# 411_AutoFan_New.net
KiCad netlist of a schematic drawn in EAGLE
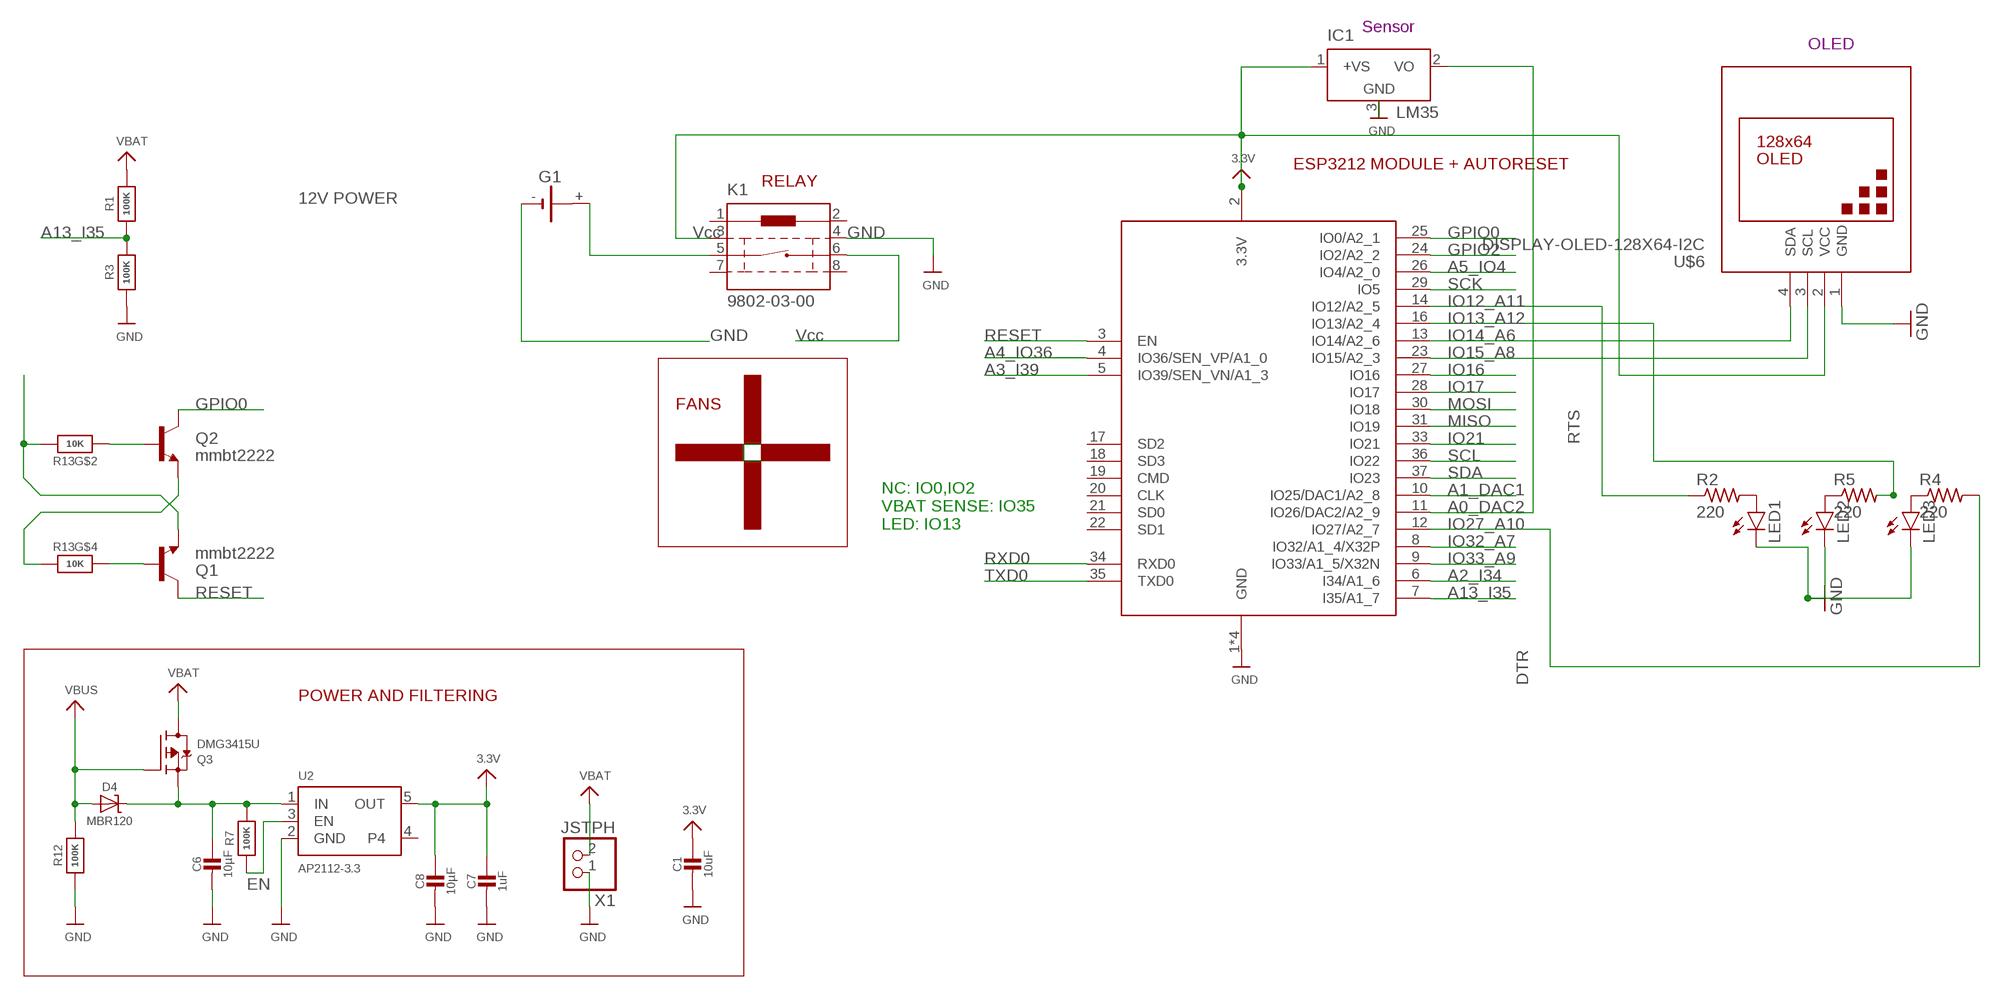
[diagram p0: schematic, sheet 1]

(export (version "E")
  (design (tool "Eeschema 10.0.6"))
  (components
    (comp (ref "C1")
      (value "10uF")
      (footprint "eagle-import:0805-NO")
      (libsource (lib "eagle-import") (part "CAP_CERAMIC0805-NOOUTLINE"))
    )
    (comp (ref "C6")
      (value "10µF")
      (footprint "eagle-import:0805-NO")
      (libsource (lib "eagle-import") (part "CAP_CERAMIC0805-NOOUTLINE"))
    )
    (comp (ref "C7")
      (value "1uF")
      (footprint "eagle-import:0603-NO")
      (libsource (lib "eagle-import") (part "CAP_CERAMIC0603_NO"))
    )
    (comp (ref "C8")
      (value "10µF")
      (footprint "eagle-import:0805-NO")
      (libsource (lib "eagle-import") (part "CAP_CERAMIC0805-NOOUTLINE"))
    )
    (comp (ref "D4")
      (value "MBR120")
      (footprint "eagle-import:SOD-123")
      (libsource (lib "eagle-import") (part "DIODE-SCHOTTKYSOD-123"))
    )
    (comp (ref "G1")
      (value "CR2032V")
      (footprint "eagle-import:CR2032V")
      (libsource (lib "eagle-import") (part "CR2032V"))
    )
    (comp (ref "IC1")
      (value "LM50")
      (footprint "eagle-import:SOT23")
      (libsource (lib "eagle-import") (part "LM50"))
    )
    (comp (ref "K1")
      (value "9802-03-00")
      (footprint "eagle-import:9802-00")
      (libsource (lib "eagle-import") (part "9802-00-03"))
    )
    (comp (ref "LED1")
      (value "LED5MM")
      (footprint "eagle-import:LED5MM")
      (libsource (lib "eagle-import") (part "LED5MM"))
    )
    (comp (ref "LED2")
      (value "LED5MM")
      (footprint "eagle-import:LED5MM")
      (libsource (lib "eagle-import") (part "LED5MM"))
    )
    (comp (ref "LED3")
      (value "LED5MM")
      (footprint "eagle-import:LED5MM")
      (libsource (lib "eagle-import") (part "LED5MM"))
    )
    (comp (ref "Q1")
      (value "mmbt2222")
      (footprint "eagle-import:SOT23-3")
      (libsource (lib "eagle-import") (part "TRANSISTOR_NPNSOT23-3"))
    )
    (comp (ref "Q2")
      (value "mmbt2222")
      (footprint "eagle-import:SOT23-3")
      (libsource (lib "eagle-import") (part "TRANSISTOR_NPNSOT23-3"))
    )
    (comp (ref "Q3")
      (value "DMG3415U")
      (footprint "eagle-import:SOT23-R")
      (libsource (lib "eagle-import") (part "MOSFET-P"))
    )
    (comp (ref "R1")
      (value "100K")
      (footprint "eagle-import:0603-NO")
      (libsource (lib "eagle-import") (part "RESISTOR_0603_NOOUT"))
    )
    (comp (ref "R2")
      (value "220")
      (footprint "eagle-import:0204_7")
      (libsource (lib "eagle-import") (part "R-US_0204/7"))
    )
    (comp (ref "R3")
      (value "100K")
      (footprint "eagle-import:0603-NO")
      (libsource (lib "eagle-import") (part "RESISTOR_0603_NOOUT"))
    )
    (comp (ref "R4")
      (value "220")
      (footprint "eagle-import:0204_7")
      (libsource (lib "eagle-import") (part "R-US_0204/7"))
    )
    (comp (ref "R5")
      (value "220")
      (footprint "eagle-import:0204_7")
      (libsource (lib "eagle-import") (part "R-US_0204/7"))
    )
    (comp (ref "R7")
      (value "100K")
      (footprint "eagle-import:0603-NO")
      (libsource (lib "eagle-import") (part "RESISTOR_0603_NOOUT"))
    )
    (comp (ref "R12")
      (value "100K")
      (footprint "eagle-import:0603-NO")
      (libsource (lib "eagle-import") (part "RESISTOR_0603_NOOUT"))
    )
    (comp (ref "R13")
      (value "10K")
      (footprint "eagle-import:RESPACK_4X0603")
      (libsource (lib "eagle-import") (part "RESISTOR_4PACK"))
    )
    (comp (ref "U$6")
      (value "DISPLAY-OLED-128X64-I2C")
      (footprint "eagle-import:DISPLAY-OLED-128X64-I2C")
      (libsource (lib "eagle-import") (part "DISPLAY-OLED-128X64-I2C"))
    )
    (comp (ref "U2")
      (value "AP2112-3.3")
      (footprint "eagle-import:SOT23-5")
      (libsource (lib "eagle-import") (part "VREG_SOT23-5"))
    )
    (comp (ref "X1")
      (value "JSTPH")
      (footprint "eagle-import:JSTPH2")
      (libsource (lib "eagle-import") (part "CON_JST_PH_2PIN"))
    )
    (comp (ref "X2")
      (value "ESP32_WROOM32_SKINNY")
      (footprint "eagle-import:WROOM32_SKINNY")
      (libsource (lib "eagle-import") (part "ESP32_WROOM32_SKINNY"))
    )
  )
  (nets
    (net (code "1") (name "/A0_DAC2") (class "Default")
      (node (ref "IC1") (pin "2") (pinfunction "VO_2") (pintype "input"))
      (node (ref "X2") (pin "11") (pinfunction "IO26/DAC2/A2_9_11") (pintype "bidirectional"))
    )
    (net (code "2") (name "/A1_DAC1") (class "Default")
      (node (ref "X2") (pin "10") (pinfunction "IO25/DAC1/A2_8_10") (pintype "bidirectional"))
    )
    (net (code "3") (name "/A2_I34") (class "Default")
      (node (ref "X2") (pin "6") (pinfunction "I34/A1_6_6") (pintype "bidirectional"))
    )
    (net (code "4") (name "/A3_I39") (class "Default")
      (node (ref "X2") (pin "5") (pinfunction "IO39/SEN_VN/A1_3_5") (pintype "passive"))
    )
    (net (code "5") (name "/A4_IO36") (class "Default")
      (node (ref "X2") (pin "4") (pinfunction "IO36/SEN_VP/A1_0_4") (pintype "passive"))
    )
    (net (code "6") (name "/A5_IO4") (class "Default")
      (node (ref "X2") (pin "26") (pinfunction "IO4/A2_0_26") (pintype "bidirectional"))
    )
    (net (code "7") (name "/A13_I35") (class "Default")
      (node (ref "R1") (pin "1") (pinfunction "1_1") (pintype "passive"))
      (node (ref "R3") (pin "2") (pinfunction "2_2") (pintype "passive"))
      (node (ref "X2") (pin "7") (pinfunction "I35/A1_7_7") (pintype "bidirectional"))
    )
    (net (code "8") (name "/DTR") (class "Default")
      (node (ref "Q2") (pin "2") (pinfunction "E_2") (pintype "passive"))
      (node (ref "R13") (pin "4") (pinfunction "1_4") (pintype "passive"))
    )
    (net (code "9") (name "/EN") (class "Default")
      (node (ref "R7") (pin "1") (pinfunction "1_1") (pintype "passive"))
      (node (ref "U2") (pin "3") (pinfunction "EN_3") (pintype "input"))
    )
    (net (code "10") (name "/GPIO0") (class "Default")
      (node (ref "Q2") (pin "3") (pinfunction "C_3") (pintype "passive"))
      (node (ref "X2") (pin "25") (pinfunction "IO0/A2_1_25") (pintype "bidirectional"))
    )
    (net (code "11") (name "/GPIO2") (class "Default")
      (node (ref "X2") (pin "24") (pinfunction "IO2/A2_2_24") (pintype "bidirectional"))
    )
    (net (code "12") (name "/IO12_A11") (class "Default")
      (node (ref "R2") (pin "1") (pinfunction "1_1") (pintype "passive"))
      (node (ref "X2") (pin "14") (pinfunction "IO12/A2_5_14") (pintype "bidirectional"))
    )
    (net (code "13") (name "/IO13_A12") (class "Default")
      (node (ref "R5") (pin "2") (pinfunction "2_2") (pintype "passive"))
      (node (ref "X2") (pin "16") (pinfunction "IO13/A2_4_16") (pintype "bidirectional"))
    )
    (net (code "14") (name "/IO14_A6") (class "Default")
      (node (ref "U$6") (pin "4") (pinfunction "SDA_4") (pintype "bidirectional"))
      (node (ref "X2") (pin "13") (pinfunction "IO14/A2_6_13") (pintype "bidirectional"))
    )
    (net (code "15") (name "/IO15_A8") (class "Default")
      (node (ref "U$6") (pin "3") (pinfunction "SCL_3") (pintype "bidirectional"))
      (node (ref "X2") (pin "23") (pinfunction "IO15/A2_3_23") (pintype "bidirectional"))
    )
    (net (code "16") (name "/IO16") (class "Default")
      (node (ref "X2") (pin "27") (pinfunction "IO16_27") (pintype "bidirectional"))
    )
    (net (code "17") (name "/IO17") (class "Default")
      (node (ref "X2") (pin "28") (pinfunction "IO17_28") (pintype "bidirectional"))
    )
    (net (code "18") (name "/IO21") (class "Default")
      (node (ref "X2") (pin "33") (pinfunction "IO21_33") (pintype "bidirectional"))
    )
    (net (code "19") (name "/IO27_A10") (class "Default")
      (node (ref "R4") (pin "2") (pinfunction "2_2") (pintype "passive"))
      (node (ref "X2") (pin "12") (pinfunction "IO27/A2_7_12") (pintype "bidirectional"))
    )
    (net (code "20") (name "/IO32_A7") (class "Default")
      (node (ref "X2") (pin "8") (pinfunction "IO32/A1_4/X32P_8") (pintype "bidirectional"))
    )
    (net (code "21") (name "/IO33_A9") (class "Default")
      (node (ref "X2") (pin "9") (pinfunction "IO33/A1_5/X32N_9") (pintype "bidirectional"))
    )
    (net (code "22") (name "/MISO") (class "Default")
      (node (ref "X2") (pin "31") (pinfunction "IO19_31") (pintype "bidirectional"))
    )
    (net (code "23") (name "/MOSI") (class "Default")
      (node (ref "X2") (pin "30") (pinfunction "IO18_30") (pintype "bidirectional"))
    )
    (net (code "24") (name "/RESET") (class "Default")
      (node (ref "Q1") (pin "3") (pinfunction "C_3") (pintype "passive"))
      (node (ref "X2") (pin "3") (pinfunction "EN_3") (pintype "input"))
    )
    (net (code "25") (name "/RTS") (class "Default")
      (node (ref "Q1") (pin "2") (pinfunction "E_2") (pintype "passive"))
      (node (ref "R13") (pin "7") (pinfunction "2_7") (pintype "passive"))
    )
    (net (code "26") (name "/RXD0") (class "Default")
      (node (ref "X2") (pin "34") (pinfunction "RXD0_34") (pintype "input"))
    )
    (net (code "27") (name "/SCK") (class "Default")
      (node (ref "X2") (pin "29") (pinfunction "IO5_29") (pintype "bidirectional"))
    )
    (net (code "28") (name "/SCL") (class "Default")
      (node (ref "X2") (pin "36") (pinfunction "IO22_36") (pintype "bidirectional"))
    )
    (net (code "29") (name "/SDA") (class "Default")
      (node (ref "X2") (pin "37") (pinfunction "IO23_37") (pintype "bidirectional"))
    )
    (net (code "30") (name "/TXD0") (class "Default")
      (node (ref "X2") (pin "35") (pinfunction "TXD0_35") (pintype "output"))
    )
    (net (code "31") (name "3.3V") (class "Default")
      (node (ref "C1") (pin "1") (pinfunction "1_1") (pintype "passive"))
      (node (ref "C7") (pin "1") (pinfunction "1_1") (pintype "passive"))
      (node (ref "C8") (pin "1") (pinfunction "1_1") (pintype "passive"))
      (node (ref "IC1") (pin "1") (pinfunction "+VS_1") (pintype "input"))
      (node (ref "K1") (pin "3") (pinfunction "3_3") (pintype "passive"))
      (node (ref "U$6") (pin "2") (pinfunction "VCC_2") (pintype "power_in"))
      (node (ref "U2") (pin "5") (pinfunction "OUT_5") (pintype "power_in"))
      (node (ref "X2") (pin "2") (pinfunction "3.3V_2") (pintype "passive"))
    )
    (net (code "32") (name "GND") (class "Default")
      (node (ref "C1") (pin "2") (pinfunction "2_2") (pintype "passive"))
      (node (ref "C6") (pin "2") (pinfunction "2_2") (pintype "passive"))
      (node (ref "C7") (pin "2") (pinfunction "2_2") (pintype "passive"))
      (node (ref "C8") (pin "2") (pinfunction "2_2") (pintype "passive"))
      (node (ref "IC1") (pin "3") (pinfunction "GND_3") (pintype "power_in"))
      (node (ref "K1") (pin "4") (pinfunction "4_4") (pintype "passive"))
      (node (ref "LED1") (pin "K") (pinfunction "C_K") (pintype "passive"))
      (node (ref "LED2") (pin "K") (pinfunction "C_K") (pintype "passive"))
      (node (ref "LED3") (pin "K") (pinfunction "C_K") (pintype "passive"))
      (node (ref "R12") (pin "1") (pinfunction "1_1") (pintype "passive"))
      (node (ref "R3") (pin "1") (pinfunction "1_1") (pintype "passive"))
      (node (ref "U$6") (pin "1") (pinfunction "GND_1") (pintype "power_in"))
      (node (ref "U2") (pin "2") (pinfunction "GND_2") (pintype "power_in"))
      (node (ref "X1") (pin "1") (pinfunction "1_1") (pintype "passive"))
      (node (ref "X2") (pin "1") (pinfunction "GND_1") (pintype "passive"))
      (node (ref "X2") (pin "15") (pinfunction "GND_15") (pintype "passive"))
      (node (ref "X2") (pin "38") (pinfunction "GND_38") (pintype "passive"))
      (node (ref "X2") (pin "P$1") (pinfunction "GND_P$1") (pintype "passive"))
    )
    (net (code "33") (name "Net-(G1-Pad+)") (class "Default")
      (node (ref "G1") (pin "+") (pinfunction "+_+") (pintype "passive"))
      (node (ref "K1") (pin "5") (pinfunction "5_5") (pintype "passive"))
    )
    (net (code "34") (name "Net-(LED1-PadA)") (class "Default")
      (node (ref "LED1") (pin "A") (pinfunction "A_A") (pintype "passive"))
      (node (ref "R2") (pin "2") (pinfunction "2_2") (pintype "passive"))
    )
    (net (code "35") (name "Net-(LED2-PadA)") (class "Default")
      (node (ref "LED2") (pin "A") (pinfunction "A_A") (pintype "passive"))
      (node (ref "R5") (pin "1") (pinfunction "1_1") (pintype "passive"))
    )
    (net (code "36") (name "Net-(LED3-PadA)") (class "Default")
      (node (ref "LED3") (pin "A") (pinfunction "A_A") (pintype "passive"))
      (node (ref "R4") (pin "1") (pinfunction "1_1") (pintype "passive"))
    )
    (net (code "37") (name "Net-(Q1-B)") (class "Default")
      (node (ref "Q1") (pin "1") (pinfunction "B_1") (pintype "passive"))
      (node (ref "R13") (pin "5") (pinfunction "2_5") (pintype "passive"))
    )
    (net (code "38") (name "Net-(Q2-B)") (class "Default")
      (node (ref "Q2") (pin "1") (pinfunction "B_1") (pintype "passive"))
      (node (ref "R13") (pin "2") (pinfunction "1_2") (pintype "passive"))
    )
    (net (code "39") (name "Net-(Q3-S)") (class "Default")
      (node (ref "C6") (pin "1") (pinfunction "1_1") (pintype "passive"))
      (node (ref "D4") (pin "C") (pinfunction "C_C") (pintype "passive"))
      (node (ref "Q3") (pin "2") (pinfunction "S_2") (pintype "passive"))
      (node (ref "R7") (pin "2") (pinfunction "2_2") (pintype "passive"))
      (node (ref "U2") (pin "1") (pinfunction "IN_1") (pintype "power_in"))
    )
    (net (code "40") (name "VBAT") (class "Default")
      (node (ref "Q3") (pin "3") (pinfunction "D_3") (pintype "passive"))
      (node (ref "R1") (pin "2") (pinfunction "2_2") (pintype "passive"))
      (node (ref "X1") (pin "2") (pinfunction "2_2") (pintype "passive"))
    )
    (net (code "41") (name "VBUS") (class "Default")
      (node (ref "D4") (pin "A") (pinfunction "A_A") (pintype "passive"))
      (node (ref "Q3") (pin "1") (pinfunction "G_1") (pintype "passive"))
      (node (ref "R12") (pin "2") (pinfunction "2_2") (pintype "passive"))
    )
    (net (code "42") (name "unconnected-(G1-+-Pad+@1)") (class "Default")
      (node (ref "G1") (pin "+@1") (pinfunction "+_+@1") (pintype "passive"))
    )
    (net (code "43") (name "unconnected-(G1-Pad-)") (class "Default")
      (node (ref "G1") (pin "-") (pinfunction "-_-") (pintype "passive"))
    )
    (net (code "44") (name "unconnected-(K1-Pad1)") (class "Default")
      (node (ref "K1") (pin "1") (pinfunction "1_1") (pintype "passive"))
    )
    (net (code "45") (name "unconnected-(K1-Pad2)") (class "Default")
      (node (ref "K1") (pin "2") (pinfunction "2_2") (pintype "passive"))
    )
    (net (code "46") (name "unconnected-(K1-Pad6)") (class "Default")
      (node (ref "K1") (pin "6") (pinfunction "6_6") (pintype "passive"))
    )
    (net (code "47") (name "unconnected-(K1-Pad7)") (class "Default")
      (node (ref "K1") (pin "7") (pinfunction "7_7") (pintype "passive"))
    )
    (net (code "48") (name "unconnected-(K1-Pad8)") (class "Default")
      (node (ref "K1") (pin "8") (pinfunction "8_8") (pintype "passive"))
    )
    (net (code "49") (name "unconnected-(U2-P4-Pad4)") (class "Default")
      (node (ref "U2") (pin "4") (pinfunction "P4_4") (pintype "bidirectional"))
    )
    (net (code "50") (name "unconnected-(X2-CLK-Pad20)") (class "Default")
      (node (ref "X2") (pin "20") (pinfunction "CLK_20") (pintype "bidirectional"))
    )
    (net (code "51") (name "unconnected-(X2-CMD-Pad19)") (class "Default")
      (node (ref "X2") (pin "19") (pinfunction "CMD_19") (pintype "bidirectional"))
    )
    (net (code "52") (name "unconnected-(X2-SD0-Pad21)") (class "Default")
      (node (ref "X2") (pin "21") (pinfunction "SD0_21") (pintype "bidirectional"))
    )
    (net (code "53") (name "unconnected-(X2-SD1-Pad22)") (class "Default")
      (node (ref "X2") (pin "22") (pinfunction "SD1_22") (pintype "bidirectional"))
    )
    (net (code "54") (name "unconnected-(X2-SD2-Pad17)") (class "Default")
      (node (ref "X2") (pin "17") (pinfunction "SD2_17") (pintype "bidirectional"))
    )
    (net (code "55") (name "unconnected-(X2-SD3-Pad18)") (class "Default")
      (node (ref "X2") (pin "18") (pinfunction "SD3_18") (pintype "bidirectional"))
    )
  )
)
